# latch_sdc_sch.net
KiCad netlist of a schematic drawn in Altium Designer
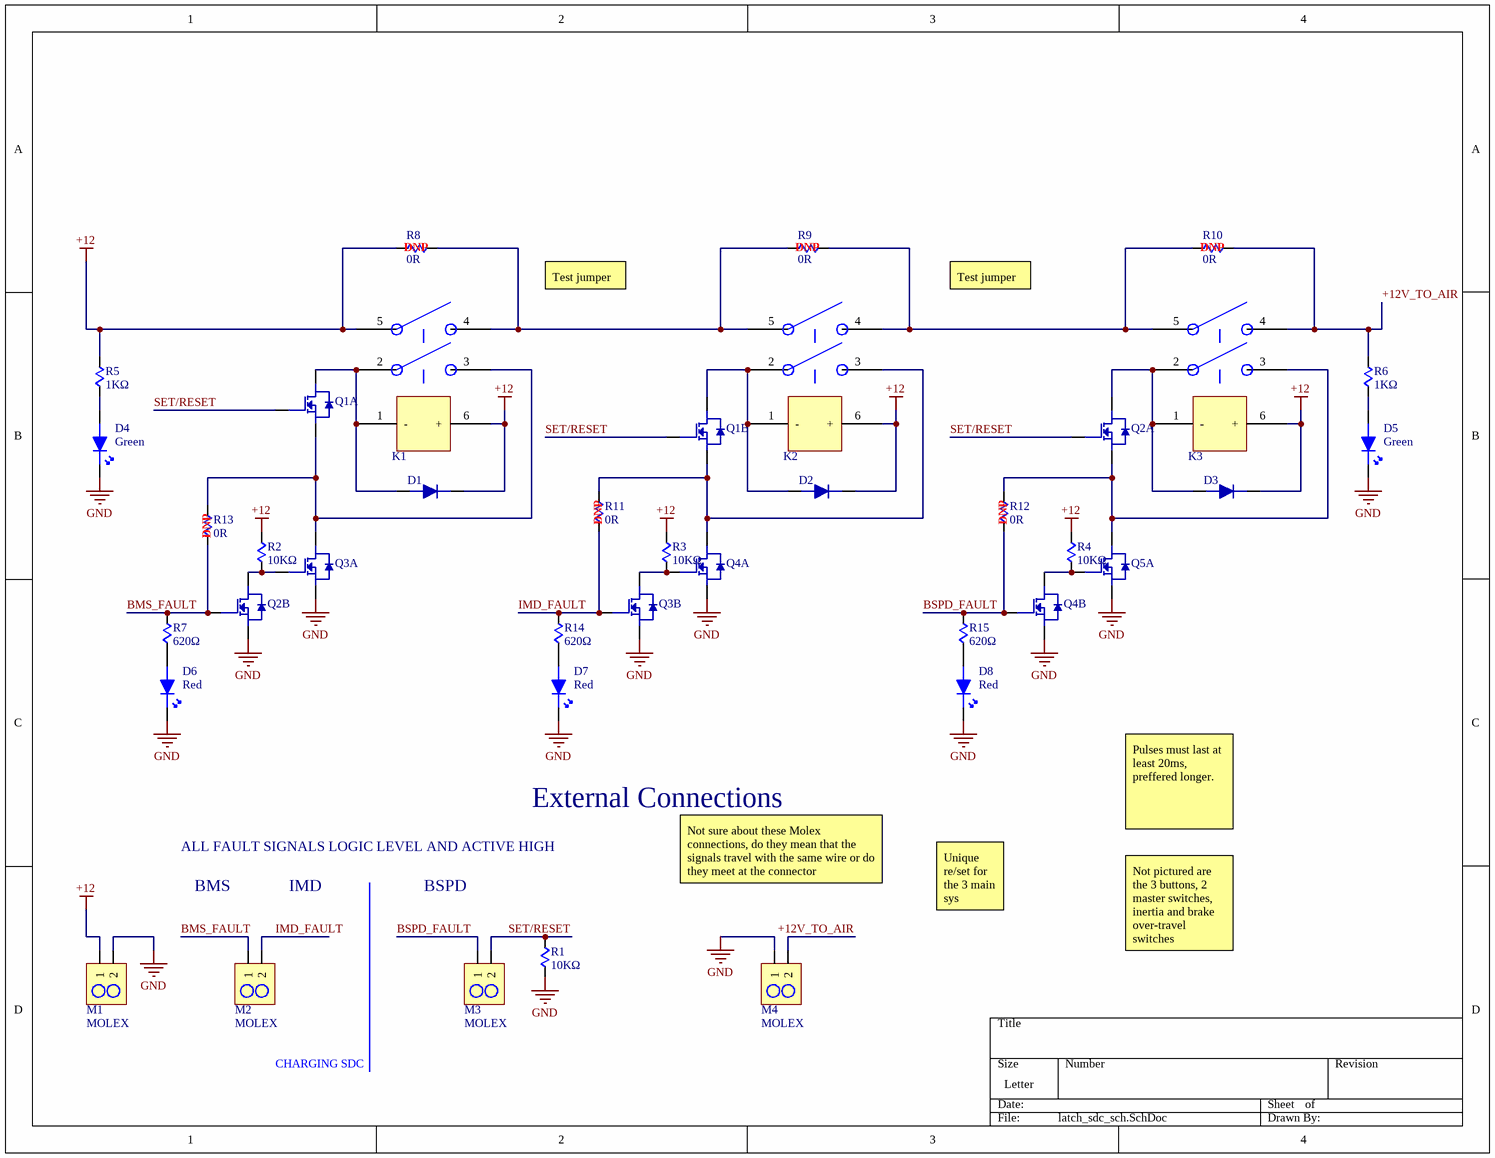
[diagram p0: latch_sdc_sch.SchDoc]

(export (version "E")
  (design (tool "Eeschema 10.0.6"))
  (components
    (comp (ref "D1")
      (value "SD560BTR")
      (footprint "DIOM4436X26N")
      (description "DIODE GEN PURP 600V 5A SMB")
      (fields (field (name "MANUFACTURER") "SMC"))
      (libsource (lib "latch_sdc_schlib") (part "SD560BTR"))
    )
    (comp (ref "D2")
      (value "SD560BTR")
      (footprint "DIOM4436X26N")
      (description "DIODE GEN PURP 600V 5A SMB")
      (fields (field (name "MANUFACTURER") "SMC"))
      (libsource (lib "latch_sdc_schlib") (part "SD560BTR"))
    )
    (comp (ref "D3")
      (value "SD560BTR")
      (footprint "DIOM4436X26N")
      (description "DIODE GEN PURP 600V 5A SMB")
      (fields (field (name "MANUFACTURER") "SMC"))
      (libsource (lib "latch_sdc_schlib") (part "SD560BTR"))
    )
    (comp (ref "D4")
      (value "Green")
      (footprint "LED GREEN")
      (description "WURTH ELEKTRONIK - 150060VS75000 - LED, 0603, B GREEN,  40MCD, 570NM")
      (libsource (lib "latch_sdc_schlib") (part "150060VS75000"))
    )
    (comp (ref "D5")
      (value "Green")
      (footprint "LED GREEN")
      (description "WURTH ELEKTRONIK - 150060VS75000 - LED, 0603, B GREEN,  40MCD, 570NM")
      (libsource (lib "latch_sdc_schlib") (part "150060VS75000"))
    )
    (comp (ref "D6")
      (value "Red")
      (footprint "LED RED")
      (description "WURTH ELEKTRONIK - 150060RS75000 - LED, 0603, RED, 250MCD, 625NM")
      (libsource (lib "latch_sdc_schlib") (part "150060RS75000"))
    )
    (comp (ref "D7")
      (value "Red")
      (footprint "LED RED")
      (description "WURTH ELEKTRONIK - 150060RS75000 - LED, 0603, RED, 250MCD, 625NM")
      (libsource (lib "latch_sdc_schlib") (part "150060RS75000"))
    )
    (comp (ref "D8")
      (value "Red")
      (footprint "LED RED")
      (description "WURTH ELEKTRONIK - 150060RS75000 - LED, 0603, RED, 250MCD, 625NM")
      (libsource (lib "latch_sdc_schlib") (part "150060RS75000"))
    )
    (comp (ref "K1")
      (value "3A")
      (footprint "RELAY02_FOOTPRINT")
      (fields
        (field (name "MANUFACTURER") "TE Connectivity")
        (field (name "MANUFACTURER PART NUMBER") "OSA-SS-212DM3,000")
      )
      (libsource (lib "latch_sdc_schlib") (part "OSA-SS-212DM3,000"))
    )
    (comp (ref "K2")
      (value "3A")
      (footprint "RELAY02_FOOTPRINT")
      (fields
        (field (name "MANUFACTURER") "TE Connectivity")
        (field (name "MANUFACTURER PART NUMBER") "OSA-SS-212DM3,000")
      )
      (libsource (lib "latch_sdc_schlib") (part "OSA-SS-212DM3,000"))
    )
    (comp (ref "K3")
      (value "3A")
      (footprint "RELAY02_FOOTPRINT")
      (fields
        (field (name "MANUFACTURER") "TE Connectivity")
        (field (name "MANUFACTURER PART NUMBER") "OSA-SS-212DM3,000")
      )
      (libsource (lib "latch_sdc_schlib") (part "OSA-SS-212DM3,000"))
    )
    (comp (ref "M1")
      (value "MOLEX")
      (footprint "MOLEX 1")
      (description "MOLEX - 43650-0200 - CONNECTOR, HEADER, 2POS, 1ROW, 3MM")
      (fields (field (name "MANUFACTURER") "Molex") (field (name "MANUFACTURER PART NUMBER") "43650-0200"))
      (libsource (lib "latch_sdc_schlib") (part "43650-0200"))
    )
    (comp (ref "M2")
      (value "MOLEX")
      (footprint "MOLEX 1")
      (description "MOLEX - 43650-0200 - CONNECTOR, HEADER, 2POS, 1ROW, 3MM")
      (fields (field (name "MANUFACTURER") "Molex") (field (name "MANUFACTURER PART NUMBER") "43650-0200"))
      (libsource (lib "latch_sdc_schlib") (part "43650-0200"))
    )
    (comp (ref "M3")
      (value "MOLEX")
      (footprint "MOLEX 1")
      (description "MOLEX - 43650-0200 - CONNECTOR, HEADER, 2POS, 1ROW, 3MM")
      (fields (field (name "MANUFACTURER") "Molex") (field (name "MANUFACTURER PART NUMBER") "43650-0200"))
      (libsource (lib "latch_sdc_schlib") (part "43650-0200"))
    )
    (comp (ref "M4")
      (value "MOLEX")
      (footprint "MOLEX 1")
      (description "MOLEX - 43650-0200 - CONNECTOR, HEADER, 2POS, 1ROW, 3MM")
      (fields (field (name "MANUFACTURER") "Molex") (field (name "MANUFACTURER PART NUMBER") "43650-0200"))
      (libsource (lib "latch_sdc_schlib") (part "43650-0200"))
    )
    (comp (ref "Q1")
      (value "DMN2029USD-13")
      (footprint "SOIC127P600X175-8N")
      (description "MOSFET 2N-CH 20V 5.8A 8SO")
      (fields (field (name "MANUFACTURER") "Diodes"))
      (libsource (lib "latch_sdc_schlib") (part "DMN2029USD-13"))
    )
    (comp (ref "Q2")
      (value "DMN2029USD-13")
      (footprint "SOIC127P600X175-8N")
      (description "MOSFET 2N-CH 20V 5.8A 8SO")
      (fields (field (name "MANUFACTURER") "Diodes"))
      (libsource (lib "latch_sdc_schlib") (part "DMN2029USD-13"))
    )
    (comp (ref "Q3")
      (value "DMN2029USD-13")
      (footprint "SOIC127P600X175-8N")
      (description "MOSFET 2N-CH 20V 5.8A 8SO")
      (fields (field (name "MANUFACTURER") "Diodes"))
      (libsource (lib "latch_sdc_schlib") (part "DMN2029USD-13"))
    )
    (comp (ref "Q4")
      (value "DMN2029USD-13")
      (footprint "SOIC127P600X175-8N")
      (description "MOSFET 2N-CH 20V 5.8A 8SO")
      (fields (field (name "MANUFACTURER") "Diodes"))
      (libsource (lib "latch_sdc_schlib") (part "DMN2029USD-13"))
    )
    (comp (ref "Q5")
      (value "DMN2029USD-13")
      (footprint "SOIC127P600X175-8N")
      (description "MOSFET 2N-CH 20V 5.8A 8SO")
      (fields (field (name "MANUFACTURER") "Diodes"))
      (libsource (lib "latch_sdc_schlib") (part "DMN2029USD-13"))
    )
    (comp (ref "R1")
      (value "10KΩ")
      (footprint "10KOHM")
      (description "RES 10K OHM 1% 1/8W 0603")
      (fields
        (field (name "MANUFACTURER") "Stackpole Electronics")
        (field (name "MANUFACTURER PART NUMBER") "RNCP0603FTD10K0")
      )
      (libsource (lib "latch_sdc_schlib") (part "RNCP0603FTD10K0"))
    )
    (comp (ref "R2")
      (value "10KΩ")
      (footprint "10KOHM")
      (description "RES 10K OHM 1% 1/8W 0603")
      (fields
        (field (name "MANUFACTURER") "Stackpole Electronics")
        (field (name "MANUFACTURER PART NUMBER") "RNCP0603FTD10K0")
      )
      (libsource (lib "latch_sdc_schlib") (part "RNCP0603FTD10K0"))
    )
    (comp (ref "R3")
      (value "10KΩ")
      (footprint "10KOHM")
      (description "RES 10K OHM 1% 1/8W 0603")
      (fields
        (field (name "MANUFACTURER") "Stackpole Electronics")
        (field (name "MANUFACTURER PART NUMBER") "RNCP0603FTD10K0")
      )
      (libsource (lib "latch_sdc_schlib") (part "RNCP0603FTD10K0"))
    )
    (comp (ref "R4")
      (value "10KΩ")
      (footprint "10KOHM")
      (description "RES 10K OHM 1% 1/8W 0603")
      (fields
        (field (name "MANUFACTURER") "Stackpole Electronics")
        (field (name "MANUFACTURER PART NUMBER") "RNCP0603FTD10K0")
      )
      (libsource (lib "latch_sdc_schlib") (part "RNCP0603FTD10K0"))
    )
    (comp (ref "R5")
      (value "1KΩ")
      (footprint "1KOHM")
      (description "YAGEO - RC0201FR-071KL - DICKSCHICHTWIDERSTAND 1K 1% 0.05W 0201")
      (fields (field (name "TOLERANCE") "1%"))
      (libsource (lib "latch_sdc_schlib") (part "RC0201FR-071KL"))
    )
    (comp (ref "R6")
      (value "1KΩ")
      (footprint "1KOHM")
      (description "YAGEO - RC0201FR-071KL - DICKSCHICHTWIDERSTAND 1K 1% 0.05W 0201")
      (fields (field (name "TOLERANCE") "1%"))
      (libsource (lib "latch_sdc_schlib") (part "RC0201FR-071KL"))
    )
    (comp (ref "R7")
      (value "620Ω")
      (footprint "620OHM")
      (description "RC0201 Series 0201 0.05 W 620 Ohms 1% ±200 ppm/°C SMT Thick Film Chip Resistor")
      (fields (field (name "TOLERANCE") "1%"))
      (libsource (lib "latch_sdc_schlib") (part "RC0201FR-07620RL"))
    )
    (comp (ref "R8")
      (value "0R")
      (footprint "0OHM")
      (description "RES 0 OHM JUMPER 1/10W 0603")
      (fields
        (field (name "MANUFACTURER") "Stackpole Electronics")
        (field (name "MANUFACTURER PART NUMBER") "RMCF0603ZT0R00")
      )
      (libsource (lib "latch_sdc_schlib") (part "RMCF0603ZT0R00_1"))
    )
    (comp (ref "R9")
      (value "0R")
      (footprint "0OHM")
      (description "RES 0 OHM JUMPER 1/10W 0603")
      (fields
        (field (name "MANUFACTURER") "Stackpole Electronics")
        (field (name "MANUFACTURER PART NUMBER") "RMCF0603ZT0R00")
      )
      (libsource (lib "latch_sdc_schlib") (part "RMCF0603ZT0R00_1"))
    )
    (comp (ref "R10")
      (value "0R")
      (footprint "0OHM")
      (description "RES 0 OHM JUMPER 1/10W 0603")
      (fields
        (field (name "MANUFACTURER") "Stackpole Electronics")
        (field (name "MANUFACTURER PART NUMBER") "RMCF0603ZT0R00")
      )
      (libsource (lib "latch_sdc_schlib") (part "RMCF0603ZT0R00_1"))
    )
    (comp (ref "R11")
      (value "0R")
      (footprint "0OHM")
      (description "RES 0 OHM JUMPER 1/10W 0603")
      (fields
        (field (name "MANUFACTURER") "Stackpole Electronics")
        (field (name "MANUFACTURER PART NUMBER") "RMCF0603ZT0R00")
      )
      (libsource (lib "latch_sdc_schlib") (part "RMCF0603ZT0R00_1"))
    )
    (comp (ref "R12")
      (value "0R")
      (footprint "0OHM")
      (description "RES 0 OHM JUMPER 1/10W 0603")
      (fields
        (field (name "MANUFACTURER") "Stackpole Electronics")
        (field (name "MANUFACTURER PART NUMBER") "RMCF0603ZT0R00")
      )
      (libsource (lib "latch_sdc_schlib") (part "RMCF0603ZT0R00_1"))
    )
    (comp (ref "R13")
      (value "0R")
      (footprint "0OHM")
      (description "RES 0 OHM JUMPER 1/10W 0603")
      (fields
        (field (name "MANUFACTURER") "Stackpole Electronics")
        (field (name "MANUFACTURER PART NUMBER") "RMCF0603ZT0R00")
      )
      (libsource (lib "latch_sdc_schlib") (part "RMCF0603ZT0R00_1"))
    )
    (comp (ref "R14")
      (value "620Ω")
      (footprint "620OHM")
      (description "RC0201 Series 0201 0.05 W 620 Ohms 1% ±200 ppm/°C SMT Thick Film Chip Resistor")
      (fields (field (name "TOLERANCE") "1%"))
      (libsource (lib "latch_sdc_schlib") (part "RC0201FR-07620RL"))
    )
    (comp (ref "R15")
      (value "620Ω")
      (footprint "620OHM")
      (description "RC0201 Series 0201 0.05 W 620 Ohms 1% ±200 ppm/°C SMT Thick Film Chip Resistor")
      (fields (field (name "TOLERANCE") "1%"))
      (libsource (lib "latch_sdc_schlib") (part "RC0201FR-07620RL"))
    )
  )
  (nets
    (net (code "1") (name "+12") (class "Default")
      (node (ref "D1") (pin "2") (pinfunction "2_2") (pintype "passive"))
      (node (ref "D2") (pin "2") (pinfunction "2_2") (pintype "passive"))
      (node (ref "D3") (pin "2") (pinfunction "2_2") (pintype "passive"))
      (node (ref "K1") (pin "5") (pintype "passive"))
      (node (ref "K1") (pin "6") (pinfunction "+_6") (pintype "passive"))
      (node (ref "K2") (pin "6") (pinfunction "+_6") (pintype "passive"))
      (node (ref "K3") (pin "6") (pinfunction "+_6") (pintype "passive"))
      (node (ref "M1") (pin "1") (pinfunction "1_1") (pintype "passive"))
      (node (ref "R2") (pin "1") (pinfunction "1_1") (pintype "passive"))
      (node (ref "R3") (pin "1") (pinfunction "1_1") (pintype "passive"))
      (node (ref "R4") (pin "1") (pinfunction "1_1") (pintype "passive"))
      (node (ref "R5") (pin "2") (pinfunction "2_2") (pintype "passive"))
      (node (ref "R8") (pin "1") (pinfunction "1_1") (pintype "passive"))
    )
    (net (code "2") (name "/+12V_TO_AIR") (class "Default")
      (node (ref "K3") (pin "4") (pintype "passive"))
      (node (ref "M4") (pin "2") (pinfunction "2_2") (pintype "passive"))
      (node (ref "R10") (pin "2") (pinfunction "2_2") (pintype "passive"))
      (node (ref "R6") (pin "2") (pinfunction "2_2") (pintype "passive"))
    )
    (net (code "3") (name "/BMS_FAULT") (class "Default")
      (node (ref "M2") (pin "1") (pinfunction "1_1") (pintype "passive"))
      (node (ref "Q2") (pin "4") (pinfunction "G2_4") (pintype "passive"))
      (node (ref "R13") (pin "1") (pinfunction "1_1") (pintype "passive"))
      (node (ref "R7") (pin "2") (pinfunction "2_2") (pintype "passive"))
    )
    (net (code "4") (name "/BSPD_FAULT") (class "Default")
      (node (ref "M3") (pin "1") (pinfunction "1_1") (pintype "passive"))
      (node (ref "Q4") (pin "4") (pinfunction "G2_4") (pintype "passive"))
      (node (ref "R12") (pin "1") (pinfunction "1_1") (pintype "passive"))
      (node (ref "R15") (pin "2") (pinfunction "2_2") (pintype "passive"))
    )
    (net (code "5") (name "/IMD_FAULT") (class "Default")
      (node (ref "M2") (pin "2") (pinfunction "2_2") (pintype "passive"))
      (node (ref "Q3") (pin "4") (pinfunction "G2_4") (pintype "passive"))
      (node (ref "R11") (pin "1") (pinfunction "1_1") (pintype "passive"))
      (node (ref "R14") (pin "2") (pinfunction "2_2") (pintype "passive"))
    )
    (net (code "6") (name "/SET{slash}RESET") (class "Default")
      (node (ref "M3") (pin "2") (pinfunction "2_2") (pintype "passive"))
      (node (ref "Q1") (pin "2") (pinfunction "G1_2") (pintype "passive"))
      (node (ref "Q1") (pin "4") (pinfunction "G2_4") (pintype "passive"))
      (node (ref "Q2") (pin "2") (pinfunction "G1_2") (pintype "passive"))
      (node (ref "R1") (pin "1") (pinfunction "1_1") (pintype "passive"))
    )
    (net (code "7") (name "GND") (class "Default")
      (node (ref "D4") (pin "2") (pinfunction "2_2") (pintype "passive"))
      (node (ref "D5") (pin "2") (pinfunction "2_2") (pintype "passive"))
      (node (ref "D6") (pin "2") (pinfunction "2_2") (pintype "passive"))
      (node (ref "D7") (pin "2") (pinfunction "2_2") (pintype "passive"))
      (node (ref "D8") (pin "2") (pinfunction "2_2") (pintype "passive"))
      (node (ref "M1") (pin "2") (pinfunction "2_2") (pintype "passive"))
      (node (ref "M4") (pin "1") (pinfunction "1_1") (pintype "passive"))
      (node (ref "Q2") (pin "3") (pinfunction "S2_3") (pintype "passive"))
      (node (ref "Q3") (pin "1") (pinfunction "S1_1") (pintype "passive"))
      (node (ref "Q3") (pin "3") (pinfunction "S2_3") (pintype "passive"))
      (node (ref "Q4") (pin "1") (pinfunction "S1_1") (pintype "passive"))
      (node (ref "Q4") (pin "3") (pinfunction "S2_3") (pintype "passive"))
      (node (ref "Q5") (pin "1") (pinfunction "S1_1") (pintype "passive"))
      (node (ref "R1") (pin "2") (pinfunction "2_2") (pintype "passive"))
    )
    (net (code "8") (name "Net-(D4-Pad1)") (class "Default")
      (node (ref "D4") (pin "1") (pinfunction "1_1") (pintype "passive"))
      (node (ref "R5") (pin "1") (pinfunction "1_1") (pintype "passive"))
    )
    (net (code "9") (name "Net-(D5-Pad1)") (class "Default")
      (node (ref "D5") (pin "1") (pinfunction "1_1") (pintype "passive"))
      (node (ref "R6") (pin "1") (pinfunction "1_1") (pintype "passive"))
    )
    (net (code "10") (name "Net-(D6-Pad1)") (class "Default")
      (node (ref "D6") (pin "1") (pinfunction "1_1") (pintype "passive"))
      (node (ref "R7") (pin "1") (pinfunction "1_1") (pintype "passive"))
    )
    (net (code "11") (name "Net-(D7-Pad1)") (class "Default")
      (node (ref "D7") (pin "1") (pinfunction "1_1") (pintype "passive"))
      (node (ref "R14") (pin "1") (pinfunction "1_1") (pintype "passive"))
    )
    (net (code "12") (name "Net-(D8-Pad1)") (class "Default")
      (node (ref "D8") (pin "1") (pinfunction "1_1") (pintype "passive"))
      (node (ref "R15") (pin "1") (pinfunction "1_1") (pintype "passive"))
    )
    (net (code "13") (name "Net-(K1--)") (class "Default")
      (node (ref "D1") (pin "1") (pinfunction "1_1") (pintype "passive"))
      (node (ref "K1") (pin "1") (pinfunction "-_1") (pintype "passive"))
      (node (ref "K1") (pin "2") (pintype "passive"))
      (node (ref "Q1") (pin "8") (pinfunction "D1_8") (pintype "passive"))
    )
    (net (code "14") (name "Net-(K1-Pad4)") (class "Default")
      (node (ref "K1") (pin "4") (pintype "passive"))
      (node (ref "K2") (pin "5") (pintype "passive"))
      (node (ref "R8") (pin "2") (pinfunction "2_2") (pintype "passive"))
      (node (ref "R9") (pin "1") (pinfunction "1_1") (pintype "passive"))
    )
    (net (code "15") (name "Net-(K2--)") (class "Default")
      (node (ref "D2") (pin "1") (pinfunction "1_1") (pintype "passive"))
      (node (ref "K2") (pin "1") (pinfunction "-_1") (pintype "passive"))
      (node (ref "K2") (pin "2") (pintype "passive"))
      (node (ref "Q1") (pin "5") (pinfunction "D2_5") (pintype "passive"))
    )
    (net (code "16") (name "Net-(K2-Pad4)") (class "Default")
      (node (ref "K2") (pin "4") (pintype "passive"))
      (node (ref "K3") (pin "5") (pintype "passive"))
      (node (ref "R10") (pin "1") (pinfunction "1_1") (pintype "passive"))
      (node (ref "R9") (pin "2") (pinfunction "2_2") (pintype "passive"))
    )
    (net (code "17") (name "Net-(K3--)") (class "Default")
      (node (ref "D3") (pin "1") (pinfunction "1_1") (pintype "passive"))
      (node (ref "K3") (pin "1") (pinfunction "-_1") (pintype "passive"))
      (node (ref "K3") (pin "2") (pintype "passive"))
      (node (ref "Q2") (pin "8") (pinfunction "D1_8") (pintype "passive"))
    )
    (net (code "18") (name "Net-(Q1A-S1)") (class "Default")
      (node (ref "K1") (pin "3") (pintype "passive"))
      (node (ref "Q1") (pin "1") (pinfunction "S1_1") (pintype "passive"))
      (node (ref "Q3") (pin "8") (pinfunction "D1_8") (pintype "passive"))
      (node (ref "R13") (pin "2") (pinfunction "2_2") (pintype "passive"))
    )
    (net (code "19") (name "Net-(Q1B-S2)") (class "Default")
      (node (ref "K2") (pin "3") (pintype "passive"))
      (node (ref "Q1") (pin "3") (pinfunction "S2_3") (pintype "passive"))
      (node (ref "Q4") (pin "8") (pinfunction "D1_8") (pintype "passive"))
      (node (ref "R11") (pin "2") (pinfunction "2_2") (pintype "passive"))
    )
    (net (code "20") (name "Net-(Q2A-S1)") (class "Default")
      (node (ref "K3") (pin "3") (pintype "passive"))
      (node (ref "Q2") (pin "1") (pinfunction "S1_1") (pintype "passive"))
      (node (ref "Q5") (pin "8") (pinfunction "D1_8") (pintype "passive"))
      (node (ref "R12") (pin "2") (pinfunction "2_2") (pintype "passive"))
    )
    (net (code "21") (name "Net-(Q2B-D2)") (class "Default")
      (node (ref "Q2") (pin "5") (pinfunction "D2_5") (pintype "passive"))
      (node (ref "Q3") (pin "2") (pinfunction "G1_2") (pintype "passive"))
      (node (ref "R2") (pin "2") (pinfunction "2_2") (pintype "passive"))
    )
    (net (code "22") (name "Net-(Q3B-D2)") (class "Default")
      (node (ref "Q3") (pin "5") (pinfunction "D2_5") (pintype "passive"))
      (node (ref "Q4") (pin "2") (pinfunction "G1_2") (pintype "passive"))
      (node (ref "R3") (pin "2") (pinfunction "2_2") (pintype "passive"))
    )
    (net (code "23") (name "Net-(Q4B-D2)") (class "Default")
      (node (ref "Q4") (pin "5") (pinfunction "D2_5") (pintype "passive"))
      (node (ref "Q5") (pin "2") (pinfunction "G1_2") (pintype "passive"))
      (node (ref "R4") (pin "2") (pinfunction "2_2") (pintype "passive"))
    )
  )
)
